# zeta2rework_lw_v23_fixes.net
KiCad netlist of a schematic drawn in EAGLE
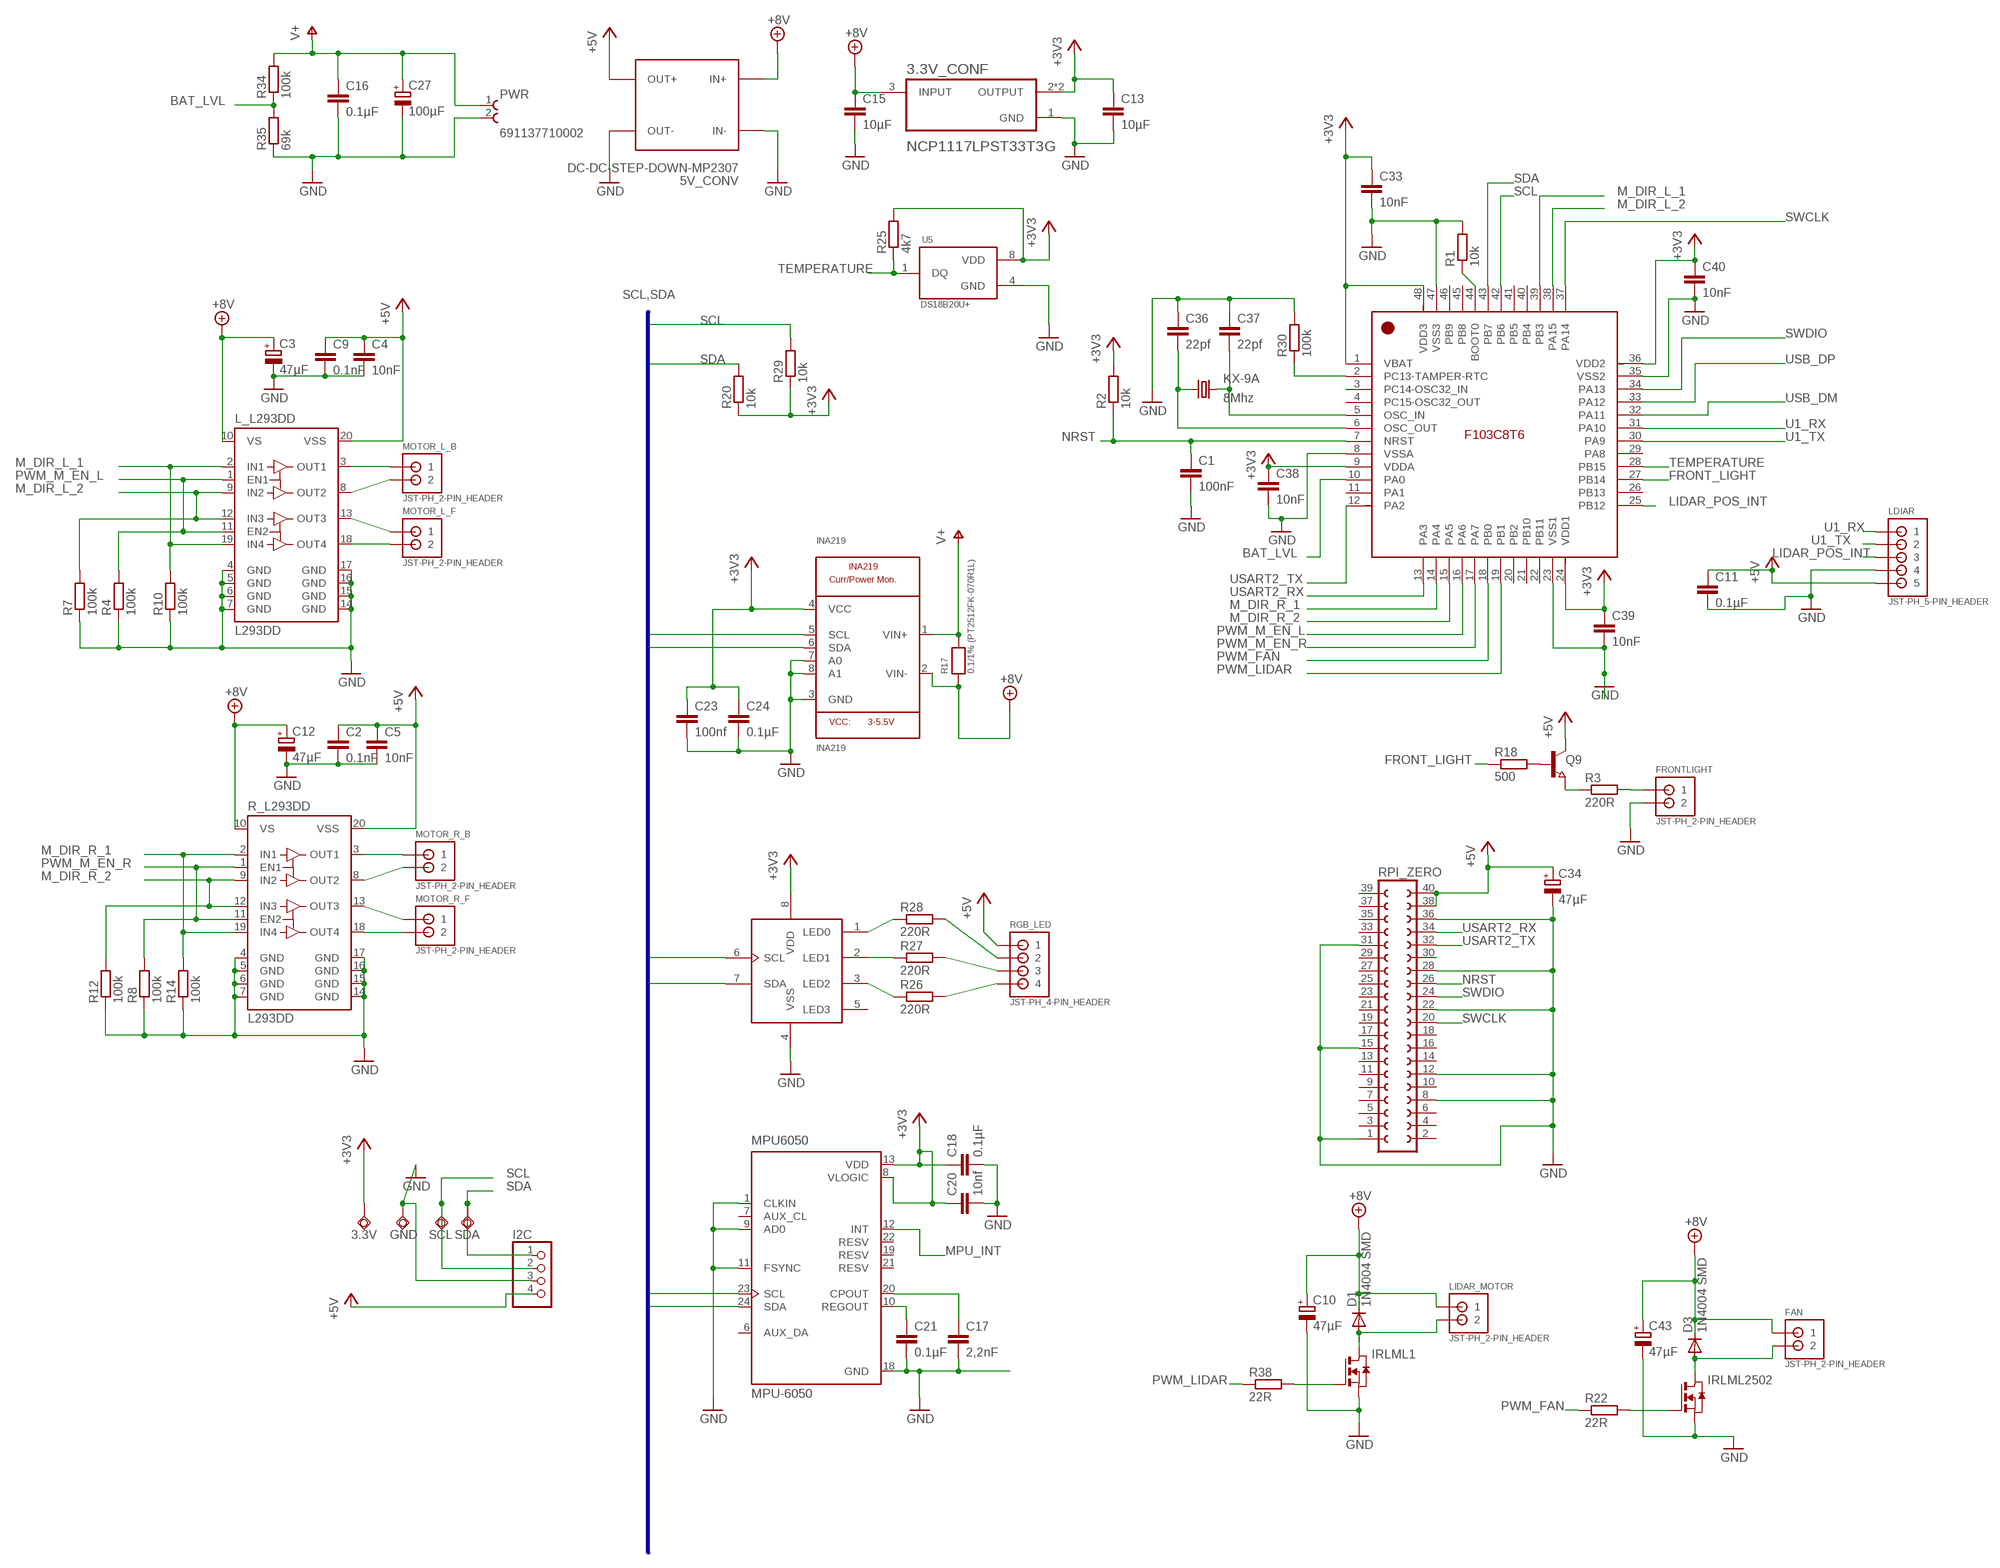
[diagram p0: schematic, sheet 1]

(export (version "E")
  (design (tool "Eeschema 10.0.6"))
  (components
    (comp (ref "3.3V")
      (value "TPSQTP20R")
      (footprint "eagle-import:TP20R")
      (libsource (lib "eagle-import") (part "TPSQTP20R"))
    )
    (comp (ref "3.3V_CONF")
      (value "NCP1117LPST33T3G")
      (footprint "eagle-import:SOT230P700X175-4N")
      (fields (field (name "MF") "ON Semiconductor"))
      (libsource (lib "eagle-import") (part "NCP1117LPST33T3G"))
    )
    (comp (ref "5V_CONV")
      (value "DC-DC-STEP-DOWN-MP2307")
      (footprint "eagle-import:DC-DC-STEP-DOWN-MP2307")
      (libsource (lib "eagle-import") (part "DC-DC-STEP-DOWN-MP2307"))
    )
    (comp (ref "C1")
      (value "100nF")
      (footprint "eagle-import:C1206")
      (libsource (lib "eagle-import") (part "C-EUC1206"))
    )
    (comp (ref "C2")
      (value "0.1nF")
      (footprint "eagle-import:C1206")
      (libsource (lib "eagle-import") (part "C-EUC1206"))
    )
    (comp (ref "C3")
      (value "47µF")
      (footprint "eagle-import:UD-4X5,8_NICHICON")
      (libsource (lib "eagle-import") (part "CPOL-EUUD-4X5,8"))
    )
    (comp (ref "C4")
      (value "10nF")
      (footprint "eagle-import:C1206")
      (libsource (lib "eagle-import") (part "C-EUC1206"))
    )
    (comp (ref "C5")
      (value "10nF")
      (footprint "eagle-import:C1206")
      (libsource (lib "eagle-import") (part "C-EUC1206"))
    )
    (comp (ref "C9")
      (value "0.1nF")
      (footprint "eagle-import:C1206")
      (libsource (lib "eagle-import") (part "C-EUC1206"))
    )
    (comp (ref "C10")
      (value "47µF")
      (footprint "eagle-import:UD-4X5,8_NICHICON")
      (libsource (lib "eagle-import") (part "CPOL-EUUD-4X5,8"))
    )
    (comp (ref "C11")
      (value "0.1µF")
      (footprint "eagle-import:C1206")
      (libsource (lib "eagle-import") (part "C-EUC1206"))
    )
    (comp (ref "C12")
      (value "47µF")
      (footprint "eagle-import:UD-4X5,8_NICHICON")
      (libsource (lib "eagle-import") (part "CPOL-EUUD-4X5,8"))
    )
    (comp (ref "C13")
      (value "10µF")
      (footprint "eagle-import:C1206")
      (libsource (lib "eagle-import") (part "C-EUC1206"))
    )
    (comp (ref "C15")
      (value "10µF")
      (footprint "eagle-import:C1206")
      (libsource (lib "eagle-import") (part "C-EUC1206"))
    )
    (comp (ref "C16")
      (value "0.1µF")
      (footprint "eagle-import:C1206")
      (libsource (lib "eagle-import") (part "C-EUC1206"))
    )
    (comp (ref "C17")
      (value "2,2nF")
      (footprint "eagle-import:C1206")
      (libsource (lib "eagle-import") (part "C-EUC1206"))
    )
    (comp (ref "C18")
      (value "0.1µF")
      (footprint "eagle-import:C1206")
      (libsource (lib "eagle-import") (part "C-EUC1206"))
    )
    (comp (ref "C20")
      (value "10nf")
      (footprint "eagle-import:C1206")
      (libsource (lib "eagle-import") (part "C-EUC1206"))
    )
    (comp (ref "C21")
      (value "0.1µF")
      (footprint "eagle-import:C1206")
      (libsource (lib "eagle-import") (part "C-EUC1206"))
    )
    (comp (ref "C23")
      (value "100nf")
      (footprint "eagle-import:C1206")
      (libsource (lib "eagle-import") (part "C-EUC1206"))
    )
    (comp (ref "C24")
      (value "0.1µF")
      (footprint "eagle-import:C1206")
      (libsource (lib "eagle-import") (part "C-EUC1206"))
    )
    (comp (ref "C27")
      (value "100µF")
      (footprint "eagle-import:UD-4X5,8_NICHICON")
      (libsource (lib "eagle-import") (part "CPOL-EUUD-4X5,8"))
    )
    (comp (ref "C33")
      (value "10nF")
      (footprint "eagle-import:C1206")
      (libsource (lib "eagle-import") (part "C-EUC1206"))
    )
    (comp (ref "C34")
      (value "47µF")
      (footprint "eagle-import:UD-4X5,8_NICHICON")
      (libsource (lib "eagle-import") (part "CPOL-EUUD-4X5,8"))
    )
    (comp (ref "C36")
      (value "22pf")
      (footprint "eagle-import:C1206")
      (libsource (lib "eagle-import") (part "C-EUC1206"))
    )
    (comp (ref "C37")
      (value "22pf")
      (footprint "eagle-import:C1206")
      (libsource (lib "eagle-import") (part "C-EUC1206"))
    )
    (comp (ref "C38")
      (value "10nF")
      (footprint "eagle-import:C1206")
      (libsource (lib "eagle-import") (part "C-EUC1206"))
    )
    (comp (ref "C39")
      (value "10nF")
      (footprint "eagle-import:C1206")
      (libsource (lib "eagle-import") (part "C-EUC1206"))
    )
    (comp (ref "C40")
      (value "10nF")
      (footprint "eagle-import:C1206")
      (libsource (lib "eagle-import") (part "C-EUC1206"))
    )
    (comp (ref "C43")
      (value "47µF")
      (footprint "eagle-import:UD-4X5,8_NICHICON")
      (libsource (lib "eagle-import") (part "CPOL-EUUD-4X5,8"))
    )
    (comp (ref "D1")
      (value "1N4004 SMD")
      (footprint "eagle-import:DO214AC")
      (libsource (lib "eagle-import") (part "DIODE-DO214AC"))
    )
    (comp (ref "D3")
      (value "1N4004 SMD")
      (footprint "eagle-import:DO214AC")
      (libsource (lib "eagle-import") (part "DIODE-DO214AC"))
    )
    (comp (ref "FAN")
      (value "JST-PH_2-PIN_HEADER")
      (footprint "eagle-import:JST_B2B-PH_HEADER")
      (libsource (lib "eagle-import") (part "JST-PH_2-PIN_HEADER"))
    )
    (comp (ref "FRONTLIGHT")
      (value "JST-PH_2-PIN_HEADER")
      (footprint "eagle-import:JST_B2B-PH_HEADER")
      (libsource (lib "eagle-import") (part "JST-PH_2-PIN_HEADER"))
    )
    (comp (ref "GND")
      (value "TPSQTP20R")
      (footprint "eagle-import:TP20R")
      (libsource (lib "eagle-import") (part "TPSQTP20R"))
    )
    (comp (ref "I2C")
      (value "PINHD-1X4")
      (footprint "eagle-import:1X04")
      (libsource (lib "eagle-import") (part "PINHD-1X4"))
    )
    (comp (ref "INA219")
      (value "INA219")
      (footprint "eagle-import:SOT23-8")
      (fields (field (name "MF") "Texas Instruments"))
      (libsource (lib "eagle-import") (part "INA219"))
    )
    (comp (ref "IRLML1")
      (value "NMOSSOT23")
      (footprint "eagle-import:SOT-23")
      (libsource (lib "eagle-import") (part "NMOSSOT23"))
    )
    (comp (ref "IRLML2502")
      (value "NMOSSOT23")
      (footprint "eagle-import:SOT-23")
      (libsource (lib "eagle-import") (part "NMOSSOT23"))
    )
    (comp (ref "KX-9A")
      (value "8Mhz")
      (footprint "eagle-import:5.0X3.2_KX-9A")
      (libsource (lib "eagle-import") (part "KX-9A"))
    )
    (comp (ref "LDIAR")
      (value "JST-PH_5-PIN_HEADER")
      (footprint "eagle-import:JST_B5B-PH_HEADER")
      (libsource (lib "eagle-import") (part "JST-PH_5-PIN_HEADER"))
    )
    (comp (ref "LIDAR_MOTOR")
      (value "JST-PH_2-PIN_HEADER")
      (footprint "eagle-import:JST_B2B-PH_HEADER")
      (libsource (lib "eagle-import") (part "JST-PH_2-PIN_HEADER"))
    )
    (comp (ref "L_L293DD")
      (value "L293DD")
      (footprint "eagle-import:SO20")
      (libsource (lib "eagle-import") (part "L293DD"))
    )
    (comp (ref "MOTOR_L_B")
      (value "JST-PH_2-PIN_HEADER")
      (footprint "eagle-import:JST_B2B-PH_HEADER")
      (libsource (lib "eagle-import") (part "JST-PH_2-PIN_HEADER"))
    )
    (comp (ref "MOTOR_L_F")
      (value "JST-PH_2-PIN_HEADER")
      (footprint "eagle-import:JST_B2B-PH_HEADER")
      (libsource (lib "eagle-import") (part "JST-PH_2-PIN_HEADER"))
    )
    (comp (ref "MOTOR_R_B")
      (value "JST-PH_2-PIN_HEADER")
      (footprint "eagle-import:JST_B2B-PH_HEADER")
      (libsource (lib "eagle-import") (part "JST-PH_2-PIN_HEADER"))
    )
    (comp (ref "MOTOR_R_F")
      (value "JST-PH_2-PIN_HEADER")
      (footprint "eagle-import:JST_B2B-PH_HEADER")
      (libsource (lib "eagle-import") (part "JST-PH_2-PIN_HEADER"))
    )
    (comp (ref "MPU6050")
      (value "MPU-6050")
      (footprint "eagle-import:QFN50P400X400X95-24N")
      (fields (field (name "MF") "TDK"))
      (libsource (lib "eagle-import") (part "MPU-6050"))
    )
    (comp (ref "PCA9533")
      (value "PCA9533")
      (footprint "eagle-import:SOIC8")
      (libsource (lib "eagle-import") (part "PCA9533"))
    )
    (comp (ref "PWR")
      (value "691137710002")
      (footprint "eagle-import:691137710002")
      (fields (field (name "MF") "Wurth Electronics"))
      (libsource (lib "eagle-import") (part "691137710002"))
    )
    (comp (ref "Q9")
      (value "NPN-TRANSISTOR_SOT23")
      (footprint "eagle-import:SOT23")
      (libsource (lib "eagle-import") (part "NPN-TRANSISTOR_SOT23"))
    )
    (comp (ref "R1")
      (value "10k")
      (footprint "eagle-import:R0603")
      (libsource (lib "eagle-import") (part "R-EU_R0603"))
    )
    (comp (ref "R2")
      (value "10k")
      (footprint "eagle-import:R0603")
      (libsource (lib "eagle-import") (part "R-EU_R0603"))
    )
    (comp (ref "R3")
      (value "220R")
      (footprint "eagle-import:R0603")
      (libsource (lib "eagle-import") (part "R-EU_R0603"))
    )
    (comp (ref "R4")
      (value "100k")
      (footprint "eagle-import:R0603")
      (libsource (lib "eagle-import") (part "R-EU_R0603"))
    )
    (comp (ref "R7")
      (value "100k")
      (footprint "eagle-import:R0603")
      (libsource (lib "eagle-import") (part "R-EU_R0603"))
    )
    (comp (ref "R8")
      (value "100k")
      (footprint "eagle-import:R0603")
      (libsource (lib "eagle-import") (part "R-EU_R0603"))
    )
    (comp (ref "R10")
      (value "100k")
      (footprint "eagle-import:R0603")
      (libsource (lib "eagle-import") (part "R-EU_R0603"))
    )
    (comp (ref "R12")
      (value "100k")
      (footprint "eagle-import:R0603")
      (libsource (lib "eagle-import") (part "R-EU_R0603"))
    )
    (comp (ref "R14")
      (value "100k")
      (footprint "eagle-import:R0603")
      (libsource (lib "eagle-import") (part "R-EU_R0603"))
    )
    (comp (ref "R17")
      (value "0.1/1% (PT2512FK-070R1L)")
      (footprint "eagle-import:2512")
      (libsource (lib "eagle-import") (part "RESISTOR2512"))
    )
    (comp (ref "R18")
      (value "500")
      (footprint "eagle-import:R0603")
      (libsource (lib "eagle-import") (part "R-EU_R0603"))
    )
    (comp (ref "R20")
      (value "10k")
      (footprint "eagle-import:R0603")
      (libsource (lib "eagle-import") (part "R-EU_R0603"))
    )
    (comp (ref "R22")
      (value "22R")
      (footprint "eagle-import:R0603")
      (libsource (lib "eagle-import") (part "R-EU_R0603"))
    )
    (comp (ref "R25")
      (value "4k7")
      (footprint "eagle-import:R0603")
      (libsource (lib "eagle-import") (part "R-EU_R0603"))
    )
    (comp (ref "R26")
      (value "220R")
      (footprint "eagle-import:R0603")
      (libsource (lib "eagle-import") (part "R-EU_R0603"))
    )
    (comp (ref "R27")
      (value "220R")
      (footprint "eagle-import:R0603")
      (libsource (lib "eagle-import") (part "R-EU_R0603"))
    )
    (comp (ref "R28")
      (value "220R")
      (footprint "eagle-import:R0603")
      (libsource (lib "eagle-import") (part "R-EU_R0603"))
    )
    (comp (ref "R29")
      (value "10k")
      (footprint "eagle-import:R0603")
      (libsource (lib "eagle-import") (part "R-EU_R0603"))
    )
    (comp (ref "R30")
      (value "100k")
      (footprint "eagle-import:R0603")
      (libsource (lib "eagle-import") (part "R-EU_R0603"))
    )
    (comp (ref "R34")
      (value "100k")
      (footprint "eagle-import:R0603")
      (libsource (lib "eagle-import") (part "R-EU_R0603"))
    )
    (comp (ref "R35")
      (value "69k")
      (footprint "eagle-import:R0603")
      (libsource (lib "eagle-import") (part "R-EU_R0603"))
    )
    (comp (ref "R38")
      (value "22R")
      (footprint "eagle-import:R0603")
      (libsource (lib "eagle-import") (part "R-EU_R0603"))
    )
    (comp (ref "RGB_LED")
      (value "JST-PH_4-PIN_HEADER")
      (footprint "eagle-import:JST_B4B-PH_HEADER")
      (libsource (lib "eagle-import") (part "JST-PH_4-PIN_HEADER"))
    )
    (comp (ref "RPI_ZERO")
      (value "FE20-2")
      (footprint "eagle-import:FE20-2")
      (libsource (lib "eagle-import") (part "FE20-2"))
    )
    (comp (ref "R_L293DD")
      (value "L293DD")
      (footprint "eagle-import:SO20")
      (libsource (lib "eagle-import") (part "L293DD"))
    )
    (comp (ref "SCL")
      (value "TPSQTP20R")
      (footprint "eagle-import:TP20R")
      (libsource (lib "eagle-import") (part "TPSQTP20R"))
    )
    (comp (ref "SDA")
      (value "TPSQTP20R")
      (footprint "eagle-import:TP20R")
      (libsource (lib "eagle-import") (part "TPSQTP20R"))
    )
    (comp (ref "STM32F103CB")
      (value "STM32F103CB")
      (footprint "eagle-import:LQFP48_7X7MM_0.5MMPP")
      (fields (field (name "MF") "STMicroelectronics") (field (name "MP") "STM32F103C8T6"))
      (libsource (lib "eagle-import") (part "STM32F103C8T6"))
    )
    (comp (ref "U5")
      (value "DS18B20U+")
      (footprint "eagle-import:SOP65P490X95-8N")
      (fields (field (name "MF") "Maxim"))
      (libsource (lib "eagle-import") (part "DS18B20U+"))
    )
  )
  (nets
    (net (code "1") (name "+3V3") (class "Default")
      (node (ref "3.3V") (pin "TP") (pinfunction "TP_TP") (pintype "input"))
      (node (ref "3.3V_CONF") (pin "2") (pinfunction "OUTPUT_2") (pintype "output"))
      (node (ref "3.3V_CONF") (pin "4") (pinfunction "OUTPUT_4") (pintype "output"))
      (node (ref "C13") (pin "1") (pinfunction "1_1") (pintype "passive"))
      (node (ref "C18") (pin "1") (pinfunction "1_1") (pintype "passive"))
      (node (ref "C20") (pin "1") (pinfunction "1_1") (pintype "passive"))
      (node (ref "C23") (pin "1") (pinfunction "1_1") (pintype "passive"))
      (node (ref "C24") (pin "1") (pinfunction "1_1") (pintype "passive"))
      (node (ref "C33") (pin "1") (pinfunction "1_1") (pintype "passive"))
      (node (ref "C38") (pin "1") (pinfunction "1_1") (pintype "passive"))
      (node (ref "C39") (pin "1") (pinfunction "1_1") (pintype "passive"))
      (node (ref "C40") (pin "1") (pinfunction "1_1") (pintype "passive"))
      (node (ref "INA219") (pin "4") (pinfunction "VCC_4") (pintype "bidirectional"))
      (node (ref "MPU6050") (pin "13") (pinfunction "VDD_13") (pintype "power_in"))
      (node (ref "MPU6050") (pin "8") (pinfunction "VLOGIC_8") (pintype "power_in"))
      (node (ref "PCA9533") (pin "8") (pinfunction "VDD_8") (pintype "power_in"))
      (node (ref "R2") (pin "2") (pinfunction "2_2") (pintype "passive"))
      (node (ref "R20") (pin "1") (pinfunction "1_1") (pintype "passive"))
      (node (ref "R25") (pin "2") (pinfunction "2_2") (pintype "passive"))
      (node (ref "R29") (pin "1") (pinfunction "1_1") (pintype "passive"))
      (node (ref "STM32F103CB") (pin "1") (pinfunction "VBAT_1") (pintype "bidirectional"))
      (node (ref "STM32F103CB") (pin "24") (pinfunction "VDD1_24") (pintype "bidirectional"))
      (node (ref "STM32F103CB") (pin "36") (pinfunction "VDD2_36") (pintype "bidirectional"))
      (node (ref "STM32F103CB") (pin "48") (pinfunction "VDD3_48") (pintype "bidirectional"))
      (node (ref "STM32F103CB") (pin "9") (pinfunction "VDDA_9") (pintype "bidirectional"))
      (node (ref "U5") (pin "8") (pinfunction "VDD_8") (pintype "power_in"))
    )
    (net (code "2") (name "+5V") (class "Default")
      (node (ref "5V_CONV") (pin "OUT+") (pinfunction "OUT+_OUT+") (pintype "bidirectional"))
      (node (ref "C11") (pin "1") (pinfunction "1_1") (pintype "passive"))
      (node (ref "C2") (pin "1") (pinfunction "1_1") (pintype "passive"))
      (node (ref "C34") (pin "+") (pinfunction "+_+") (pintype "passive"))
      (node (ref "C4") (pin "1") (pinfunction "1_1") (pintype "passive"))
      (node (ref "C5") (pin "1") (pinfunction "1_1") (pintype "passive"))
      (node (ref "C9") (pin "1") (pinfunction "1_1") (pintype "passive"))
      (node (ref "I2C") (pin "4") (pinfunction "4_4") (pintype "passive"))
      (node (ref "LDIAR") (pin "P5") (pinfunction "5_P5") (pintype "bidirectional"))
      (node (ref "L_L293DD") (pin "20") (pinfunction "VSS_20") (pintype "power_in"))
      (node (ref "Q9") (pin "3") (pinfunction "C_3") (pintype "passive"))
      (node (ref "RGB_LED") (pin "P1") (pinfunction "1_P1") (pintype "bidirectional"))
      (node (ref "RPI_ZERO") (pin "38") (pinfunction "38_38") (pintype "passive"))
      (node (ref "RPI_ZERO") (pin "40") (pinfunction "40_40") (pintype "passive"))
      (node (ref "R_L293DD") (pin "20") (pinfunction "VSS_20") (pintype "power_in"))
    )
    (net (code "3") (name "+8V") (class "Default")
      (node (ref "3.3V_CONF") (pin "3") (pinfunction "INPUT_3") (pintype "input"))
      (node (ref "5V_CONV") (pin "IN+") (pinfunction "IN+_IN+") (pintype "bidirectional"))
      (node (ref "C10") (pin "+") (pinfunction "+_+") (pintype "passive"))
      (node (ref "C12") (pin "+") (pinfunction "+_+") (pintype "passive"))
      (node (ref "C15") (pin "1") (pinfunction "1_1") (pintype "passive"))
      (node (ref "C3") (pin "+") (pinfunction "+_+") (pintype "passive"))
      (node (ref "C43") (pin "+") (pinfunction "+_+") (pintype "passive"))
      (node (ref "D1") (pin "C") (pinfunction "C_C") (pintype "passive"))
      (node (ref "D3") (pin "C") (pinfunction "C_C") (pintype "passive"))
      (node (ref "FAN") (pin "P1") (pinfunction "1_P1") (pintype "bidirectional"))
      (node (ref "INA219") (pin "2") (pinfunction "VIN-_2") (pintype "bidirectional"))
      (node (ref "LIDAR_MOTOR") (pin "P1") (pinfunction "1_P1") (pintype "bidirectional"))
      (node (ref "L_L293DD") (pin "10") (pinfunction "VS_10") (pintype "power_in"))
      (node (ref "R17") (pin "1") (pinfunction "1_1") (pintype "passive"))
      (node (ref "R_L293DD") (pin "10") (pinfunction "VS_10") (pintype "power_in"))
    )
    (net (code "4") (name "/BAT_LVL") (class "Default")
      (node (ref "R34") (pin "1") (pinfunction "1_1") (pintype "passive"))
      (node (ref "R35") (pin "2") (pinfunction "2_2") (pintype "passive"))
      (node (ref "STM32F103CB") (pin "10") (pinfunction "PA0_10") (pintype "bidirectional"))
    )
    (net (code "5") (name "/FRONT_LIGHT") (class "Default")
      (node (ref "R18") (pin "1") (pinfunction "1_1") (pintype "passive"))
      (node (ref "STM32F103CB") (pin "27") (pinfunction "PB14_27") (pintype "bidirectional"))
    )
    (net (code "6") (name "/LIDAR_POS_INT") (class "Default")
      (node (ref "LDIAR") (pin "P3") (pinfunction "3_P3") (pintype "bidirectional"))
      (node (ref "STM32F103CB") (pin "25") (pinfunction "PB12_25") (pintype "bidirectional"))
    )
    (net (code "7") (name "/MPU_INT") (class "Default")
      (node (ref "MPU6050") (pin "12") (pinfunction "INT_12") (pintype "output"))
    )
    (net (code "8") (name "/M_DIR_L_1") (class "Default")
      (node (ref "L_L293DD") (pin "19") (pinfunction "IN4_19") (pintype "input"))
      (node (ref "L_L293DD") (pin "2") (pinfunction "IN1_2") (pintype "input"))
      (node (ref "R10") (pin "2") (pinfunction "2_2") (pintype "passive"))
      (node (ref "STM32F103CB") (pin "39") (pinfunction "PB3_39") (pintype "bidirectional"))
    )
    (net (code "9") (name "/M_DIR_L_2") (class "Default")
      (node (ref "L_L293DD") (pin "12") (pinfunction "IN3_12") (pintype "input"))
      (node (ref "L_L293DD") (pin "9") (pinfunction "IN2_9") (pintype "input"))
      (node (ref "R7") (pin "2") (pinfunction "2_2") (pintype "passive"))
      (node (ref "STM32F103CB") (pin "38") (pinfunction "PA15_38") (pintype "bidirectional"))
    )
    (net (code "10") (name "/M_DIR_R_1") (class "Default")
      (node (ref "R14") (pin "2") (pinfunction "2_2") (pintype "passive"))
      (node (ref "R_L293DD") (pin "19") (pinfunction "IN4_19") (pintype "input"))
      (node (ref "R_L293DD") (pin "2") (pinfunction "IN1_2") (pintype "input"))
      (node (ref "STM32F103CB") (pin "14") (pinfunction "PA4_14") (pintype "bidirectional"))
    )
    (net (code "11") (name "/M_DIR_R_2") (class "Default")
      (node (ref "R12") (pin "2") (pinfunction "2_2") (pintype "passive"))
      (node (ref "R_L293DD") (pin "12") (pinfunction "IN3_12") (pintype "input"))
      (node (ref "R_L293DD") (pin "9") (pinfunction "IN2_9") (pintype "input"))
      (node (ref "STM32F103CB") (pin "15") (pinfunction "PA5_15") (pintype "bidirectional"))
    )
    (net (code "12") (name "/NRST") (class "Default")
      (node (ref "C1") (pin "1") (pinfunction "1_1") (pintype "passive"))
      (node (ref "R2") (pin "1") (pinfunction "1_1") (pintype "passive"))
      (node (ref "RPI_ZERO") (pin "26") (pinfunction "26_26") (pintype "passive"))
      (node (ref "STM32F103CB") (pin "7") (pinfunction "NRST_7") (pintype "bidirectional"))
    )
    (net (code "13") (name "/PWM_FAN") (class "Default")
      (node (ref "R22") (pin "1") (pinfunction "1_1") (pintype "passive"))
      (node (ref "STM32F103CB") (pin "18") (pinfunction "PB0_18") (pintype "bidirectional"))
    )
    (net (code "14") (name "/PWM_LIDAR") (class "Default")
      (node (ref "R38") (pin "1") (pinfunction "1_1") (pintype "passive"))
      (node (ref "STM32F103CB") (pin "19") (pinfunction "PB1_19") (pintype "bidirectional"))
    )
    (net (code "15") (name "/PWM_M_EN_L") (class "Default")
      (node (ref "L_L293DD") (pin "1") (pinfunction "EN1_1") (pintype "input"))
      (node (ref "L_L293DD") (pin "11") (pinfunction "EN2_11") (pintype "input"))
      (node (ref "R4") (pin "2") (pinfunction "2_2") (pintype "passive"))
      (node (ref "STM32F103CB") (pin "16") (pinfunction "PA6_16") (pintype "bidirectional"))
    )
    (net (code "16") (name "/PWM_M_EN_R") (class "Default")
      (node (ref "R8") (pin "2") (pinfunction "2_2") (pintype "passive"))
      (node (ref "R_L293DD") (pin "1") (pinfunction "EN1_1") (pintype "input"))
      (node (ref "R_L293DD") (pin "11") (pinfunction "EN2_11") (pintype "input"))
      (node (ref "STM32F103CB") (pin "17") (pinfunction "PA7_17") (pintype "bidirectional"))
    )
    (net (code "17") (name "/SCL") (class "Default")
      (node (ref "I2C") (pin "2") (pinfunction "2_2") (pintype "passive"))
      (node (ref "INA219") (pin "5") (pinfunction "SCL_5") (pintype "bidirectional"))
      (node (ref "MPU6050") (pin "23") (pinfunction "SCL_23") (pintype "input"))
      (node (ref "PCA9533") (pin "6") (pinfunction "SCL_6") (pintype "input"))
      (node (ref "R29") (pin "2") (pinfunction "2_2") (pintype "passive"))
      (node (ref "SCL") (pin "TP") (pinfunction "TP_TP") (pintype "input"))
      (node (ref "STM32F103CB") (pin "42") (pinfunction "PB6_42") (pintype "bidirectional"))
    )
    (net (code "18") (name "/SDA") (class "Default")
      (node (ref "I2C") (pin "1") (pinfunction "1_1") (pintype "passive"))
      (node (ref "INA219") (pin "6") (pinfunction "SDA_6") (pintype "bidirectional"))
      (node (ref "MPU6050") (pin "24") (pinfunction "SDA_24") (pintype "bidirectional"))
      (node (ref "PCA9533") (pin "7") (pinfunction "SDA_7") (pintype "bidirectional"))
      (node (ref "R20") (pin "2") (pinfunction "2_2") (pintype "passive"))
      (node (ref "SDA") (pin "TP") (pinfunction "TP_TP") (pintype "input"))
      (node (ref "STM32F103CB") (pin "43") (pinfunction "PB7_43") (pintype "bidirectional"))
    )
    (net (code "19") (name "/SWCLK") (class "Default")
      (node (ref "RPI_ZERO") (pin "20") (pinfunction "20_20") (pintype "passive"))
      (node (ref "STM32F103CB") (pin "37") (pinfunction "PA14_37") (pintype "bidirectional"))
    )
    (net (code "20") (name "/SWDIO") (class "Default")
      (node (ref "RPI_ZERO") (pin "24") (pinfunction "24_24") (pintype "passive"))
      (node (ref "STM32F103CB") (pin "34") (pinfunction "PA13_34") (pintype "bidirectional"))
    )
    (net (code "21") (name "/TEMPERATURE") (class "Default")
      (node (ref "R25") (pin "1") (pinfunction "1_1") (pintype "passive"))
      (node (ref "STM32F103CB") (pin "28") (pinfunction "PB15_28") (pintype "bidirectional"))
      (node (ref "U5") (pin "1") (pinfunction "DQ_1") (pintype "bidirectional"))
    )
    (net (code "22") (name "/U1_RX") (class "Default")
      (node (ref "LDIAR") (pin "P1") (pinfunction "1_P1") (pintype "bidirectional"))
      (node (ref "STM32F103CB") (pin "31") (pinfunction "PA10_31") (pintype "bidirectional"))
    )
    (net (code "23") (name "/U1_TX") (class "Default")
      (node (ref "LDIAR") (pin "P2") (pinfunction "2_P2") (pintype "bidirectional"))
      (node (ref "STM32F103CB") (pin "30") (pinfunction "PA9_30") (pintype "bidirectional"))
    )
    (net (code "24") (name "/USART2_RX") (class "Default")
      (node (ref "RPI_ZERO") (pin "34") (pinfunction "34_34") (pintype "passive"))
      (node (ref "STM32F103CB") (pin "13") (pinfunction "PA3_13") (pintype "bidirectional"))
    )
    (net (code "25") (name "/USART2_TX") (class "Default")
      (node (ref "RPI_ZERO") (pin "32") (pinfunction "32_32") (pintype "passive"))
      (node (ref "STM32F103CB") (pin "12") (pinfunction "PA2_12") (pintype "bidirectional"))
    )
    (net (code "26") (name "/USB_DM") (class "Default")
      (node (ref "STM32F103CB") (pin "32") (pinfunction "PA11_32") (pintype "bidirectional"))
    )
    (net (code "27") (name "/USB_DP") (class "Default")
      (node (ref "STM32F103CB") (pin "33") (pinfunction "PA12_33") (pintype "bidirectional"))
    )
    (net (code "29") (name "GND") (class "Default")
      (node (ref "3.3V_CONF") (pin "1") (pinfunction "GND_1") (pintype "power_in"))
      (node (ref "5V_CONV") (pin "IN-") (pinfunction "IN-_IN-") (pintype "bidirectional"))
      (node (ref "5V_CONV") (pin "OUT-") (pinfunction "OUT-_OUT-") (pintype "bidirectional"))
      (node (ref "C1") (pin "2") (pinfunction "2_2") (pintype "passive"))
      (node (ref "C10") (pin "-") (pinfunction "-_-") (pintype "passive"))
      (node (ref "C11") (pin "2") (pinfunction "2_2") (pintype "passive"))
      (node (ref "C12") (pin "-") (pinfunction "-_-") (pintype "passive"))
      (node (ref "C13") (pin "2") (pinfunction "2_2") (pintype "passive"))
      (node (ref "C15") (pin "2") (pinfunction "2_2") (pintype "passive"))
      (node (ref "C16") (pin "2") (pinfunction "2_2") (pintype "passive"))
      (node (ref "C17") (pin "2") (pinfunction "2_2") (pintype "passive"))
      (node (ref "C18") (pin "2") (pinfunction "2_2") (pintype "passive"))
      (node (ref "C2") (pin "2") (pinfunction "2_2") (pintype "passive"))
      (node (ref "C20") (pin "2") (pinfunction "2_2") (pintype "passive"))
      (node (ref "C21") (pin "2") (pinfunction "2_2") (pintype "passive"))
      (node (ref "C23") (pin "2") (pinfunction "2_2") (pintype "passive"))
      (node (ref "C24") (pin "2") (pinfunction "2_2") (pintype "passive"))
      (node (ref "C27") (pin "-") (pinfunction "-_-") (pintype "passive"))
      (node (ref "C3") (pin "-") (pinfunction "-_-") (pintype "passive"))
      (node (ref "C33") (pin "2") (pinfunction "2_2") (pintype "passive"))
      (node (ref "C34") (pin "-") (pinfunction "-_-") (pintype "passive"))
      (node (ref "C36") (pin "1") (pinfunction "1_1") (pintype "passive"))
      (node (ref "C37") (pin "1") (pinfunction "1_1") (pintype "passive"))
      (node (ref "C38") (pin "2") (pinfunction "2_2") (pintype "passive"))
      (node (ref "C39") (pin "2") (pinfunction "2_2") (pintype "passive"))
      (node (ref "C4") (pin "2") (pinfunction "2_2") (pintype "passive"))
      (node (ref "C40") (pin "2") (pinfunction "2_2") (pintype "passive"))
      (node (ref "C43") (pin "-") (pinfunction "-_-") (pintype "passive"))
      (node (ref "C5") (pin "2") (pinfunction "2_2") (pintype "passive"))
      (node (ref "C9") (pin "2") (pinfunction "2_2") (pintype "passive"))
      (node (ref "FRONTLIGHT") (pin "P2") (pinfunction "2_P2") (pintype "bidirectional"))
      (node (ref "GND") (pin "TP") (pinfunction "TP_TP") (pintype "input"))
      (node (ref "I2C") (pin "3") (pinfunction "3_3") (pintype "passive"))
      (node (ref "INA219") (pin "3") (pinfunction "GND_3") (pintype "bidirectional"))
      (node (ref "INA219") (pin "7") (pinfunction "A0_7") (pintype "bidirectional"))
      (node (ref "INA219") (pin "8") (pinfunction "A1_8") (pintype "bidirectional"))
      (node (ref "IRLML1") (pin "2") (pinfunction "S_2") (pintype "passive"))
      (node (ref "IRLML2502") (pin "2") (pinfunction "S_2") (pintype "passive"))
      (node (ref "LDIAR") (pin "P4") (pinfunction "4_P4") (pintype "bidirectional"))
      (node (ref "L_L293DD") (pin "14") (pinfunction "GND_14") (pintype "power_in"))
      (node (ref "L_L293DD") (pin "15") (pinfunction "GND_15") (pintype "power_in"))
      (node (ref "L_L293DD") (pin "16") (pinfunction "GND_16") (pintype "power_in"))
      (node (ref "L_L293DD") (pin "17") (pinfunction "GND_17") (pintype "power_in"))
      (node (ref "L_L293DD") (pin "4") (pinfunction "GND_4") (pintype "power_in"))
      (node (ref "L_L293DD") (pin "5") (pinfunction "GND_5") (pintype "power_in"))
      (node (ref "L_L293DD") (pin "6") (pinfunction "GND_6") (pintype "power_in"))
      (node (ref "L_L293DD") (pin "7") (pinfunction "GND_7") (pintype "power_in"))
      (node (ref "MPU6050") (pin "1") (pinfunction "CLKIN_1") (pintype "input"))
      (node (ref "MPU6050") (pin "11") (pinfunction "FSYNC_11") (pintype "input"))
      (node (ref "MPU6050") (pin "18") (pinfunction "GND_18") (pintype "power_in"))
      (node (ref "MPU6050") (pin "9") (pinfunction "AD0_9") (pintype "input"))
      (node (ref "PCA9533") (pin "4") (pinfunction "VSS_4") (pintype "power_in"))
      (node (ref "PWR") (pin "2") (pinfunction "2_2") (pintype "passive"))
      (node (ref "R1") (pin "2") (pinfunction "2_2") (pintype "passive"))
      (node (ref "R10") (pin "1") (pinfunction "1_1") (pintype "passive"))
      (node (ref "R12") (pin "1") (pinfunction "1_1") (pintype "passive"))
      (node (ref "R14") (pin "1") (pinfunction "1_1") (pintype "passive"))
      (node (ref "R30") (pin "2") (pinfunction "2_2") (pintype "passive"))
      (node (ref "R35") (pin "1") (pinfunction "1_1") (pintype "passive"))
      (node (ref "R4") (pin "1") (pinfunction "1_1") (pintype "passive"))
      (node (ref "R7") (pin "1") (pinfunction "1_1") (pintype "passive"))
      (node (ref "R8") (pin "1") (pinfunction "1_1") (pintype "passive"))
      (node (ref "RPI_ZERO") (pin "1") (pinfunction "1_1") (pintype "passive"))
      (node (ref "RPI_ZERO") (pin "12") (pinfunction "12_12") (pintype "passive"))
      (node (ref "RPI_ZERO") (pin "15") (pinfunction "15_15") (pintype "passive"))
      (node (ref "RPI_ZERO") (pin "22") (pinfunction "22_22") (pintype "passive"))
      (node (ref "RPI_ZERO") (pin "28") (pinfunction "28_28") (pintype "passive"))
      (node (ref "RPI_ZERO") (pin "31") (pinfunction "31_31") (pintype "passive"))
      (node (ref "RPI_ZERO") (pin "36") (pinfunction "36_36") (pintype "passive"))
      (node (ref "RPI_ZERO") (pin "8") (pinfunction "8_8") (pintype "passive"))
      (node (ref "R_L293DD") (pin "14") (pinfunction "GND_14") (pintype "power_in"))
      (node (ref "R_L293DD") (pin "15") (pinfunction "GND_15") (pintype "power_in"))
      (node (ref "R_L293DD") (pin "16") (pinfunction "GND_16") (pintype "power_in"))
      (node (ref "R_L293DD") (pin "17") (pinfunction "GND_17") (pintype "power_in"))
      (node (ref "R_L293DD") (pin "4") (pinfunction "GND_4") (pintype "power_in"))
      (node (ref "R_L293DD") (pin "5") (pinfunction "GND_5") (pintype "power_in"))
      (node (ref "R_L293DD") (pin "6") (pinfunction "GND_6") (pintype "power_in"))
      (node (ref "R_L293DD") (pin "7") (pinfunction "GND_7") (pintype "power_in"))
      (node (ref "STM32F103CB") (pin "23") (pinfunction "VSS1_23") (pintype "bidirectional"))
      (node (ref "STM32F103CB") (pin "35") (pinfunction "VSS2_35") (pintype "bidirectional"))
      (node (ref "STM32F103CB") (pin "47") (pinfunction "VSS3_47") (pintype "bidirectional"))
      (node (ref "STM32F103CB") (pin "8") (pinfunction "VSSA_8") (pintype "bidirectional"))
      (node (ref "U5") (pin "4") (pinfunction "GND_4") (pintype "power_in"))
    )
    (net (code "30") (name "Net-(FAN-2)") (class "Default")
      (node (ref "D3") (pin "A") (pinfunction "A_A") (pintype "passive"))
      (node (ref "FAN") (pin "P2") (pinfunction "2_P2") (pintype "bidirectional"))
      (node (ref "IRLML2502") (pin "1") (pinfunction "D_1") (pintype "passive"))
    )
    (net (code "31") (name "Net-(FRONTLIGHT-1)") (class "Default")
      (node (ref "FRONTLIGHT") (pin "P1") (pinfunction "1_P1") (pintype "bidirectional"))
      (node (ref "R3") (pin "2") (pinfunction "2_2") (pintype "passive"))
    )
    (net (code "32") (name "Net-(IRLML1-D)") (class "Default")
      (node (ref "D1") (pin "A") (pinfunction "A_A") (pintype "passive"))
      (node (ref "IRLML1") (pin "1") (pinfunction "D_1") (pintype "passive"))
      (node (ref "LIDAR_MOTOR") (pin "P2") (pinfunction "2_P2") (pintype "bidirectional"))
    )
    (net (code "33") (name "Net-(IRLML1-G)") (class "Default")
      (node (ref "IRLML1") (pin "3") (pinfunction "G_3") (pintype "passive"))
      (node (ref "R38") (pin "2") (pinfunction "2_2") (pintype "passive"))
    )
    (net (code "34") (name "Net-(IRLML2502-G)") (class "Default")
      (node (ref "IRLML2502") (pin "3") (pinfunction "G_3") (pintype "passive"))
      (node (ref "R22") (pin "2") (pinfunction "2_2") (pintype "passive"))
    )
    (net (code "35") (name "Net-(KX-9A-2)") (class "Default")
      (node (ref "C37") (pin "2") (pinfunction "2_2") (pintype "passive"))
      (node (ref "KX-9A") (pin "3") (pinfunction "2_3") (pintype "passive"))
      (node (ref "STM32F103CB") (pin "5") (pinfunction "OSC_IN_5") (pintype "bidirectional"))
    )
    (net (code "36") (name "Net-(L_L293DD-OUT1)") (class "Default")
      (node (ref "L_L293DD") (pin "3") (pinfunction "OUT1_3") (pintype "output"))
      (node (ref "MOTOR_L_B") (pin "P1") (pinfunction "1_P1") (pintype "bidirectional"))
    )
    (net (code "37") (name "Net-(L_L293DD-OUT2)") (class "Default")
      (node (ref "L_L293DD") (pin "8") (pinfunction "OUT2_8") (pintype "output"))
      (node (ref "MOTOR_L_B") (pin "P2") (pinfunction "2_P2") (pintype "bidirectional"))
    )
    (net (code "38") (name "Net-(L_L293DD-OUT3)") (class "Default")
      (node (ref "L_L293DD") (pin "13") (pinfunction "OUT3_13") (pintype "output"))
      (node (ref "MOTOR_L_F") (pin "P1") (pinfunction "1_P1") (pintype "bidirectional"))
    )
    (net (code "39") (name "Net-(L_L293DD-OUT4)") (class "Default")
      (node (ref "L_L293DD") (pin "18") (pinfunction "OUT4_18") (pintype "output"))
      (node (ref "MOTOR_L_F") (pin "P2") (pinfunction "2_P2") (pintype "bidirectional"))
    )
    (net (code "40") (name "Net-(MOTOR_R_B-1)") (class "Default")
      (node (ref "MOTOR_R_B") (pin "P1") (pinfunction "1_P1") (pintype "bidirectional"))
      (node (ref "R_L293DD") (pin "3") (pinfunction "OUT1_3") (pintype "output"))
    )
    (net (code "41") (name "Net-(MOTOR_R_B-2)") (class "Default")
      (node (ref "MOTOR_R_B") (pin "P2") (pinfunction "2_P2") (pintype "bidirectional"))
      (node (ref "R_L293DD") (pin "8") (pinfunction "OUT2_8") (pintype "output"))
    )
    (net (code "42") (name "Net-(MOTOR_R_F-1)") (class "Default")
      (node (ref "MOTOR_R_F") (pin "P1") (pinfunction "1_P1") (pintype "bidirectional"))
      (node (ref "R_L293DD") (pin "13") (pinfunction "OUT3_13") (pintype "output"))
    )
    (net (code "43") (name "Net-(MOTOR_R_F-2)") (class "Default")
      (node (ref "MOTOR_R_F") (pin "P2") (pinfunction "2_P2") (pintype "bidirectional"))
      (node (ref "R_L293DD") (pin "18") (pinfunction "OUT4_18") (pintype "output"))
    )
    (net (code "44") (name "Net-(MPU6050-CPOUT)") (class "Default")
      (node (ref "C17") (pin "1") (pinfunction "1_1") (pintype "passive"))
      (node (ref "MPU6050") (pin "20") (pinfunction "CPOUT_20") (pintype "passive"))
    )
    (net (code "45") (name "Net-(MPU6050-REGOUT)") (class "Default")
      (node (ref "C21") (pin "1") (pinfunction "1_1") (pintype "passive"))
      (node (ref "MPU6050") (pin "10") (pinfunction "REGOUT_10") (pintype "passive"))
    )
    (net (code "46") (name "Net-(PCA9533-LED0)") (class "Default")
      (node (ref "PCA9533") (pin "1") (pinfunction "LED0_1") (pintype "bidirectional"))
      (node (ref "R28") (pin "1") (pinfunction "1_1") (pintype "passive"))
    )
    (net (code "47") (name "Net-(PCA9533-LED1)") (class "Default")
      (node (ref "PCA9533") (pin "2") (pinfunction "LED1_2") (pintype "bidirectional"))
      (node (ref "R27") (pin "1") (pinfunction "1_1") (pintype "passive"))
    )
    (net (code "48") (name "Net-(PCA9533-LED2)") (class "Default")
      (node (ref "PCA9533") (pin "3") (pinfunction "LED2_3") (pintype "bidirectional"))
      (node (ref "R26") (pin "1") (pinfunction "1_1") (pintype "passive"))
    )
    (net (code "49") (name "Net-(Q9-B)") (class "Default")
      (node (ref "Q9") (pin "1") (pinfunction "B_1") (pintype "passive"))
      (node (ref "R18") (pin "2") (pinfunction "2_2") (pintype "passive"))
    )
    (net (code "50") (name "Net-(Q9-E)") (class "Default")
      (node (ref "Q9") (pin "2") (pinfunction "E_2") (pintype "passive"))
      (node (ref "R3") (pin "1") (pinfunction "1_1") (pintype "passive"))
    )
    (net (code "51") (name "Net-(RGB_LED-2)") (class "Default")
      (node (ref "R28") (pin "2") (pinfunction "2_2") (pintype "passive"))
      (node (ref "RGB_LED") (pin "P2") (pinfunction "2_P2") (pintype "bidirectional"))
    )
    (net (code "52") (name "Net-(RGB_LED-3)") (class "Default")
      (node (ref "R27") (pin "2") (pinfunction "2_2") (pintype "passive"))
      (node (ref "RGB_LED") (pin "P3") (pinfunction "3_P3") (pintype "bidirectional"))
    )
    (net (code "53") (name "Net-(RGB_LED-4)") (class "Default")
      (node (ref "R26") (pin "2") (pinfunction "2_2") (pintype "passive"))
      (node (ref "RGB_LED") (pin "P4") (pinfunction "4_P4") (pintype "bidirectional"))
    )
    (net (code "54") (name "Net-(STM32F103CB-BOOT0)") (class "Default")
      (node (ref "R1") (pin "1") (pinfunction "1_1") (pintype "passive"))
      (node (ref "STM32F103CB") (pin "44") (pinfunction "BOOT0_44") (pintype "bidirectional"))
    )
    (net (code "55") (name "Net-(STM32F103CB-OSC_OUT)") (class "Default")
      (node (ref "C36") (pin "2") (pinfunction "2_2") (pintype "passive"))
      (node (ref "KX-9A") (pin "1") (pinfunction "1_1") (pintype "passive"))
      (node (ref "STM32F103CB") (pin "6") (pinfunction "OSC_OUT_6") (pintype "bidirectional"))
    )
    (net (code "56") (name "Net-(STM32F103CB-PC13-TAMPER-RTC)") (class "Default")
      (node (ref "R30") (pin "1") (pinfunction "1_1") (pintype "passive"))
      (node (ref "STM32F103CB") (pin "2") (pinfunction "PC13-TAMPER-RTC_2") (pintype "bidirectional"))
    )
    (net (code "57") (name "V+") (class "Default")
      (node (ref "C16") (pin "1") (pinfunction "1_1") (pintype "passive"))
      (node (ref "C27") (pin "+") (pinfunction "+_+") (pintype "passive"))
      (node (ref "INA219") (pin "1") (pinfunction "VIN+_1") (pintype "bidirectional"))
      (node (ref "PWR") (pin "1") (pinfunction "1_1") (pintype "passive"))
      (node (ref "R17") (pin "2") (pinfunction "2_2") (pintype "passive"))
      (node (ref "R34") (pin "2") (pinfunction "2_2") (pintype "passive"))
    )
    (net (code "58") (name "unconnected-(MPU6050-AUX_CL-Pad7)") (class "Default")
      (node (ref "MPU6050") (pin "7") (pinfunction "AUX_CL_7") (pintype "input"))
    )
    (net (code "59") (name "unconnected-(MPU6050-AUX_DA-Pad6)") (class "Default")
      (node (ref "MPU6050") (pin "6") (pinfunction "AUX_DA_6") (pintype "bidirectional"))
    )
    (net (code "60") (name "unconnected-(MPU6050-RESV-Pad19)") (class "Default")
      (node (ref "MPU6050") (pin "19") (pinfunction "RESV_19") (pintype "passive"))
    )
    (net (code "61") (name "unconnected-(MPU6050-RESV-Pad21)") (class "Default")
      (node (ref "MPU6050") (pin "21") (pinfunction "RESV_21") (pintype "passive"))
    )
    (net (code "62") (name "unconnected-(MPU6050-RESV-Pad22)") (class "Default")
      (node (ref "MPU6050") (pin "22") (pinfunction "RESV_22") (pintype "passive"))
    )
    (net (code "63") (name "unconnected-(PCA9533-LED3-Pad5)") (class "Default")
      (node (ref "PCA9533") (pin "5") (pinfunction "LED3_5") (pintype "bidirectional"))
    )
    (net (code "64") (name "unconnected-(RPI_ZERO-Pad2)") (class "Default")
      (node (ref "RPI_ZERO") (pin "2") (pinfunction "2_2") (pintype "passive"))
    )
    (net (code "65") (name "unconnected-(RPI_ZERO-Pad3)") (class "Default")
      (node (ref "RPI_ZERO") (pin "3") (pinfunction "3_3") (pintype "passive"))
    )
    (net (code "66") (name "unconnected-(RPI_ZERO-Pad4)") (class "Default")
      (node (ref "RPI_ZERO") (pin "4") (pinfunction "4_4") (pintype "passive"))
    )
    (net (code "67") (name "unconnected-(RPI_ZERO-Pad5)") (class "Default")
      (node (ref "RPI_ZERO") (pin "5") (pinfunction "5_5") (pintype "passive"))
    )
    (net (code "68") (name "unconnected-(RPI_ZERO-Pad6)") (class "Default")
      (node (ref "RPI_ZERO") (pin "6") (pinfunction "6_6") (pintype "passive"))
    )
    (net (code "69") (name "unconnected-(RPI_ZERO-Pad7)") (class "Default")
      (node (ref "RPI_ZERO") (pin "7") (pinfunction "7_7") (pintype "passive"))
    )
    (net (code "70") (name "unconnected-(RPI_ZERO-Pad9)") (class "Default")
      (node (ref "RPI_ZERO") (pin "9") (pinfunction "9_9") (pintype "passive"))
    )
    (net (code "71") (name "unconnected-(RPI_ZERO-Pad10)") (class "Default")
      (node (ref "RPI_ZERO") (pin "10") (pinfunction "10_10") (pintype "passive"))
    )
    (net (code "72") (name "unconnected-(RPI_ZERO-Pad11)") (class "Default")
      (node (ref "RPI_ZERO") (pin "11") (pinfunction "11_11") (pintype "passive"))
    )
    (net (code "73") (name "unconnected-(RPI_ZERO-Pad13)") (class "Default")
      (node (ref "RPI_ZERO") (pin "13") (pinfunction "13_13") (pintype "passive"))
    )
    (net (code "74") (name "unconnected-(RPI_ZERO-Pad14)") (class "Default")
      (node (ref "RPI_ZERO") (pin "14") (pinfunction "14_14") (pintype "passive"))
    )
    (net (code "75") (name "unconnected-(RPI_ZERO-Pad16)") (class "Default")
      (node (ref "RPI_ZERO") (pin "16") (pinfunction "16_16") (pintype "passive"))
    )
    (net (code "76") (name "unconnected-(RPI_ZERO-Pad17)") (class "Default")
      (node (ref "RPI_ZERO") (pin "17") (pinfunction "17_17") (pintype "passive"))
    )
    (net (code "77") (name "unconnected-(RPI_ZERO-Pad18)") (class "Default")
      (node (ref "RPI_ZERO") (pin "18") (pinfunction "18_18") (pintype "passive"))
    )
    (net (code "78") (name "unconnected-(RPI_ZERO-Pad19)") (class "Default")
      (node (ref "RPI_ZERO") (pin "19") (pinfunction "19_19") (pintype "passive"))
    )
    (net (code "79") (name "unconnected-(RPI_ZERO-Pad21)") (class "Default")
      (node (ref "RPI_ZERO") (pin "21") (pinfunction "21_21") (pintype "passive"))
    )
    (net (code "80") (name "unconnected-(RPI_ZERO-Pad23)") (class "Default")
      (node (ref "RPI_ZERO") (pin "23") (pinfunction "23_23") (pintype "passive"))
    )
    (net (code "81") (name "unconnected-(RPI_ZERO-Pad25)") (class "Default")
      (node (ref "RPI_ZERO") (pin "25") (pinfunction "25_25") (pintype "passive"))
    )
    (net (code "82") (name "unconnected-(RPI_ZERO-Pad27)") (class "Default")
      (node (ref "RPI_ZERO") (pin "27") (pinfunction "27_27") (pintype "passive"))
    )
    (net (code "83") (name "unconnected-(RPI_ZERO-Pad29)") (class "Default")
      (node (ref "RPI_ZERO") (pin "29") (pinfunction "29_29") (pintype "passive"))
    )
    (net (code "84") (name "unconnected-(RPI_ZERO-Pad30)") (class "Default")
      (node (ref "RPI_ZERO") (pin "30") (pinfunction "30_30") (pintype "passive"))
    )
    (net (code "85") (name "unconnected-(RPI_ZERO-Pad33)") (class "Default")
      (node (ref "RPI_ZERO") (pin "33") (pinfunction "33_33") (pintype "passive"))
    )
    (net (code "86") (name "unconnected-(RPI_ZERO-Pad35)") (class "Default")
      (node (ref "RPI_ZERO") (pin "35") (pinfunction "35_35") (pintype "passive"))
    )
    (net (code "87") (name "unconnected-(RPI_ZERO-Pad37)") (class "Default")
      (node (ref "RPI_ZERO") (pin "37") (pinfunction "37_37") (pintype "passive"))
    )
    (net (code "88") (name "unconnected-(RPI_ZERO-Pad39)") (class "Default")
      (node (ref "RPI_ZERO") (pin "39") (pinfunction "39_39") (pintype "passive"))
    )
    (net (code "89") (name "unconnected-(STM32F103CB-PA1-Pad11)") (class "Default")
      (node (ref "STM32F103CB") (pin "11") (pinfunction "PA1_11") (pintype "bidirectional"))
    )
    (net (code "90") (name "unconnected-(STM32F103CB-PA8-Pad29)") (class "Default")
      (node (ref "STM32F103CB") (pin "29") (pinfunction "PA8_29") (pintype "bidirectional"))
    )
    (net (code "91") (name "unconnected-(STM32F103CB-PB2-Pad20)") (class "Default")
      (node (ref "STM32F103CB") (pin "20") (pinfunction "PB2_20") (pintype "bidirectional"))
    )
    (net (code "92") (name "unconnected-(STM32F103CB-PB4-Pad40)") (class "Default")
      (node (ref "STM32F103CB") (pin "40") (pinfunction "PB4_40") (pintype "bidirectional"))
    )
    (net (code "93") (name "unconnected-(STM32F103CB-PB5-Pad41)") (class "Default")
      (node (ref "STM32F103CB") (pin "41") (pinfunction "PB5_41") (pintype "bidirectional"))
    )
    (net (code "94") (name "unconnected-(STM32F103CB-PB8-Pad45)") (class "Default")
      (node (ref "STM32F103CB") (pin "45") (pinfunction "PB8_45") (pintype "bidirectional"))
    )
    (net (code "95") (name "unconnected-(STM32F103CB-PB9-Pad46)") (class "Default")
      (node (ref "STM32F103CB") (pin "46") (pinfunction "PB9_46") (pintype "bidirectional"))
    )
    (net (code "96") (name "unconnected-(STM32F103CB-PB10-Pad21)") (class "Default")
      (node (ref "STM32F103CB") (pin "21") (pinfunction "PB10_21") (pintype "bidirectional"))
    )
    (net (code "97") (name "unconnected-(STM32F103CB-PB11-Pad22)") (class "Default")
      (node (ref "STM32F103CB") (pin "22") (pinfunction "PB11_22") (pintype "bidirectional"))
    )
    (net (code "98") (name "unconnected-(STM32F103CB-PB13-Pad26)") (class "Default")
      (node (ref "STM32F103CB") (pin "26") (pinfunction "PB13_26") (pintype "bidirectional"))
    )
    (net (code "99") (name "unconnected-(STM32F103CB-PC14-OSC32_IN-Pad3)") (class "Default")
      (node (ref "STM32F103CB") (pin "3") (pinfunction "PC14-OSC32_IN_3") (pintype "bidirectional"))
    )
    (net (code "100") (name "unconnected-(STM32F103CB-PC15-OSC32_OUT-Pad4)") (class "Default")
      (node (ref "STM32F103CB") (pin "4") (pinfunction "PC15-OSC32_OUT_4") (pintype "bidirectional"))
    )
  )
)
